# amp_msgeq7_v_1_0.net
KiCad netlist of a schematic drawn in EAGLE
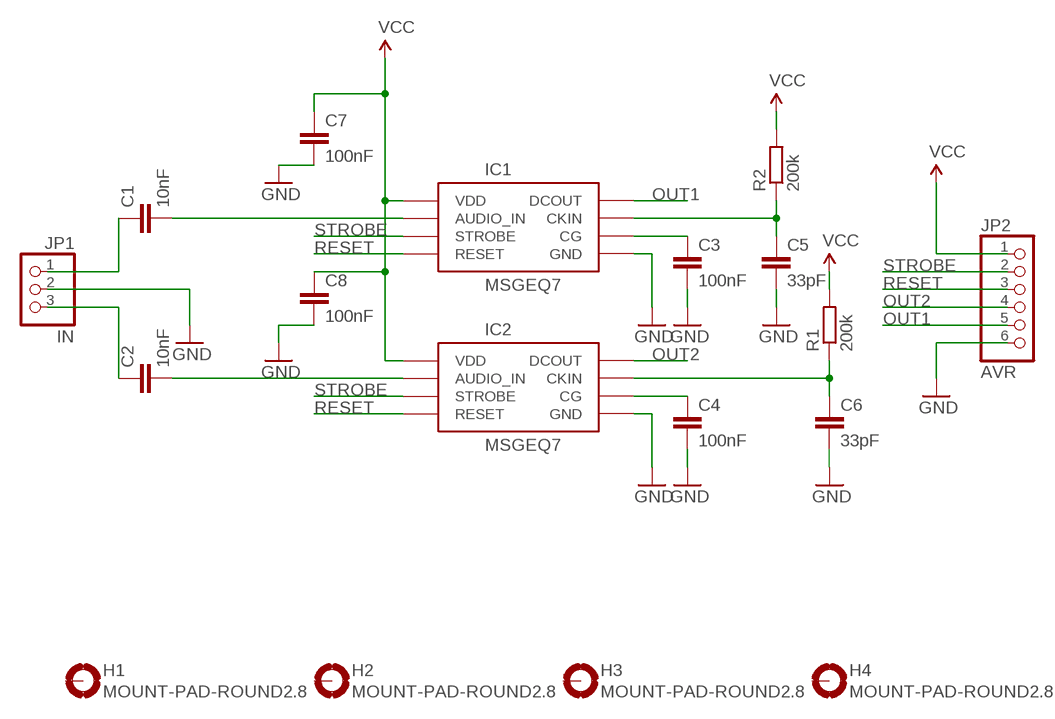
[diagram p0: schematic, sheet 1]

(export (version "E")
  (design (tool "Eeschema 10.0.6"))
  (components
    (comp (ref "C1")
      (value "10nF")
      (footprint "eagle-import:C025-030X050")
      (libsource (lib "eagle-import") (part "C-EU025-030X050"))
    )
    (comp (ref "C2")
      (value "10nF")
      (footprint "eagle-import:C025-030X050")
      (libsource (lib "eagle-import") (part "C-EU025-030X050"))
    )
    (comp (ref "C3")
      (value "100nF")
      (footprint "eagle-import:C025-030X050")
      (libsource (lib "eagle-import") (part "C-EU025-030X050"))
    )
    (comp (ref "C4")
      (value "100nF")
      (footprint "eagle-import:C025-030X050")
      (libsource (lib "eagle-import") (part "C-EU025-030X050"))
    )
    (comp (ref "C5")
      (value "33pF")
      (footprint "eagle-import:C025-030X050")
      (libsource (lib "eagle-import") (part "C-EU025-030X050"))
    )
    (comp (ref "C6")
      (value "33pF")
      (footprint "eagle-import:C025-030X050")
      (libsource (lib "eagle-import") (part "C-EU025-030X050"))
    )
    (comp (ref "C7")
      (value "100nF")
      (footprint "eagle-import:C025-025X050")
      (libsource (lib "eagle-import") (part "C-EU025-025X050"))
    )
    (comp (ref "C8")
      (value "100nF")
      (footprint "eagle-import:C025-025X050")
      (libsource (lib "eagle-import") (part "C-EU025-025X050"))
    )
    (comp (ref "H1")
      (value "MOUNT-PAD-ROUND2.8")
      (footprint "eagle-import:2,8-PAD")
      (libsource (lib "eagle-import") (part "MOUNT-PAD-ROUND2.8"))
    )
    (comp (ref "H2")
      (value "MOUNT-PAD-ROUND2.8")
      (footprint "eagle-import:2,8-PAD")
      (libsource (lib "eagle-import") (part "MOUNT-PAD-ROUND2.8"))
    )
    (comp (ref "H3")
      (value "MOUNT-PAD-ROUND2.8")
      (footprint "eagle-import:2,8-PAD")
      (libsource (lib "eagle-import") (part "MOUNT-PAD-ROUND2.8"))
    )
    (comp (ref "H4")
      (value "MOUNT-PAD-ROUND2.8")
      (footprint "eagle-import:2,8-PAD")
      (libsource (lib "eagle-import") (part "MOUNT-PAD-ROUND2.8"))
    )
    (comp (ref "IC1")
      (value "MSGEQ7DIP")
      (footprint "eagle-import:DIL08")
      (libsource (lib "eagle-import") (part "MSGEQ7DIP"))
    )
    (comp (ref "IC2")
      (value "MSGEQ7DIP")
      (footprint "eagle-import:DIL08")
      (libsource (lib "eagle-import") (part "MSGEQ7DIP"))
    )
    (comp (ref "JP1")
      (value "IN")
      (footprint "eagle-import:1X03")
      (libsource (lib "eagle-import") (part "PINHD-1X3"))
    )
    (comp (ref "JP2")
      (value "AVR")
      (footprint "eagle-import:1X06")
      (libsource (lib "eagle-import") (part "PINHD-1X6"))
    )
    (comp (ref "R1")
      (value "200k")
      (footprint "eagle-import:0204_7")
      (libsource (lib "eagle-import") (part "R-EU_0204/7"))
    )
    (comp (ref "R2")
      (value "200k")
      (footprint "eagle-import:0204_7")
      (libsource (lib "eagle-import") (part "R-EU_0204/7"))
    )
  )
  (nets
    (net (code "1") (name "/OUT1") (class "Default")
      (node (ref "IC1") (pin "3") (pinfunction "DCOUT_3") (pintype "bidirectional"))
      (node (ref "JP2") (pin "5") (pinfunction "5_5") (pintype "passive"))
    )
    (net (code "2") (name "/OUT2") (class "Default")
      (node (ref "IC2") (pin "3") (pinfunction "DCOUT_3") (pintype "bidirectional"))
      (node (ref "JP2") (pin "4") (pinfunction "4_4") (pintype "passive"))
    )
    (net (code "3") (name "/RESET") (class "Default")
      (node (ref "IC1") (pin "7") (pinfunction "RESET_7") (pintype "input"))
      (node (ref "IC2") (pin "7") (pinfunction "RESET_7") (pintype "input"))
      (node (ref "JP2") (pin "3") (pinfunction "3_3") (pintype "passive"))
    )
    (net (code "4") (name "/STROBE") (class "Default")
      (node (ref "IC1") (pin "4") (pinfunction "STROBE_4") (pintype "input"))
      (node (ref "IC2") (pin "4") (pinfunction "STROBE_4") (pintype "input"))
      (node (ref "JP2") (pin "2") (pinfunction "2_2") (pintype "passive"))
    )
    (net (code "5") (name "GND") (class "Default")
      (node (ref "C3") (pin "2") (pinfunction "2_2") (pintype "passive"))
      (node (ref "C4") (pin "2") (pinfunction "2_2") (pintype "passive"))
      (node (ref "C5") (pin "2") (pinfunction "2_2") (pintype "passive"))
      (node (ref "C6") (pin "2") (pinfunction "2_2") (pintype "passive"))
      (node (ref "C7") (pin "2") (pinfunction "2_2") (pintype "passive"))
      (node (ref "C8") (pin "2") (pinfunction "2_2") (pintype "passive"))
      (node (ref "IC1") (pin "2") (pinfunction "GND_2") (pintype "bidirectional"))
      (node (ref "IC2") (pin "2") (pinfunction "GND_2") (pintype "bidirectional"))
      (node (ref "JP1") (pin "2") (pinfunction "2_2") (pintype "passive"))
      (node (ref "JP2") (pin "6") (pinfunction "6_6") (pintype "passive"))
    )
    (net (code "6") (name "Net-(C1-Pad1)") (class "Default")
      (node (ref "C1") (pin "1") (pinfunction "1_1") (pintype "passive"))
      (node (ref "JP1") (pin "1") (pinfunction "1_1") (pintype "passive"))
    )
    (net (code "7") (name "Net-(C2-Pad1)") (class "Default")
      (node (ref "C2") (pin "1") (pinfunction "1_1") (pintype "passive"))
      (node (ref "JP1") (pin "3") (pinfunction "3_3") (pintype "passive"))
    )
    (net (code "8") (name "Net-(IC1-AUDIO_IN)") (class "Default")
      (node (ref "C1") (pin "2") (pinfunction "2_2") (pintype "passive"))
      (node (ref "IC1") (pin "5") (pinfunction "AUDIO_IN_5") (pintype "input"))
    )
    (net (code "9") (name "Net-(IC1-CG)") (class "Default")
      (node (ref "C3") (pin "1") (pinfunction "1_1") (pintype "passive"))
      (node (ref "IC1") (pin "6") (pinfunction "CG_6") (pintype "bidirectional"))
    )
    (net (code "10") (name "Net-(IC1-CKIN)") (class "Default")
      (node (ref "C5") (pin "1") (pinfunction "1_1") (pintype "passive"))
      (node (ref "IC1") (pin "8") (pinfunction "CKIN_8") (pintype "bidirectional"))
      (node (ref "R2") (pin "1") (pinfunction "1_1") (pintype "passive"))
    )
    (net (code "11") (name "Net-(IC2-AUDIO_IN)") (class "Default")
      (node (ref "C2") (pin "2") (pinfunction "2_2") (pintype "passive"))
      (node (ref "IC2") (pin "5") (pinfunction "AUDIO_IN_5") (pintype "input"))
    )
    (net (code "12") (name "Net-(IC2-CG)") (class "Default")
      (node (ref "C4") (pin "1") (pinfunction "1_1") (pintype "passive"))
      (node (ref "IC2") (pin "6") (pinfunction "CG_6") (pintype "bidirectional"))
    )
    (net (code "13") (name "Net-(IC2-CKIN)") (class "Default")
      (node (ref "C6") (pin "1") (pinfunction "1_1") (pintype "passive"))
      (node (ref "IC2") (pin "8") (pinfunction "CKIN_8") (pintype "bidirectional"))
      (node (ref "R1") (pin "1") (pinfunction "1_1") (pintype "passive"))
    )
    (net (code "14") (name "VCC") (class "Default")
      (node (ref "C7") (pin "1") (pinfunction "1_1") (pintype "passive"))
      (node (ref "C8") (pin "1") (pinfunction "1_1") (pintype "passive"))
      (node (ref "IC1") (pin "1") (pinfunction "VDD_1") (pintype "input"))
      (node (ref "IC2") (pin "1") (pinfunction "VDD_1") (pintype "input"))
      (node (ref "JP2") (pin "1") (pinfunction "1_1") (pintype "passive"))
      (node (ref "R1") (pin "2") (pinfunction "2_2") (pintype "passive"))
      (node (ref "R2") (pin "2") (pinfunction "2_2") (pintype "passive"))
    )
    (net (code "15") (name "unconnected-(H1-MOUNT-PadB2,8)") (class "Default")
      (node (ref "H1") (pin "B2,8") (pinfunction "MOUNT_B2,8") (pintype "passive"))
    )
    (net (code "16") (name "unconnected-(H2-MOUNT-PadB2,8)") (class "Default")
      (node (ref "H2") (pin "B2,8") (pinfunction "MOUNT_B2,8") (pintype "passive"))
    )
    (net (code "17") (name "unconnected-(H3-MOUNT-PadB2,8)") (class "Default")
      (node (ref "H3") (pin "B2,8") (pinfunction "MOUNT_B2,8") (pintype "passive"))
    )
    (net (code "18") (name "unconnected-(H4-MOUNT-PadB2,8)") (class "Default")
      (node (ref "H4") (pin "B2,8") (pinfunction "MOUNT_B2,8") (pintype "passive"))
    )
  )
)
